# basic_micro.net
KiCad netlist of a schematic drawn in EAGLE
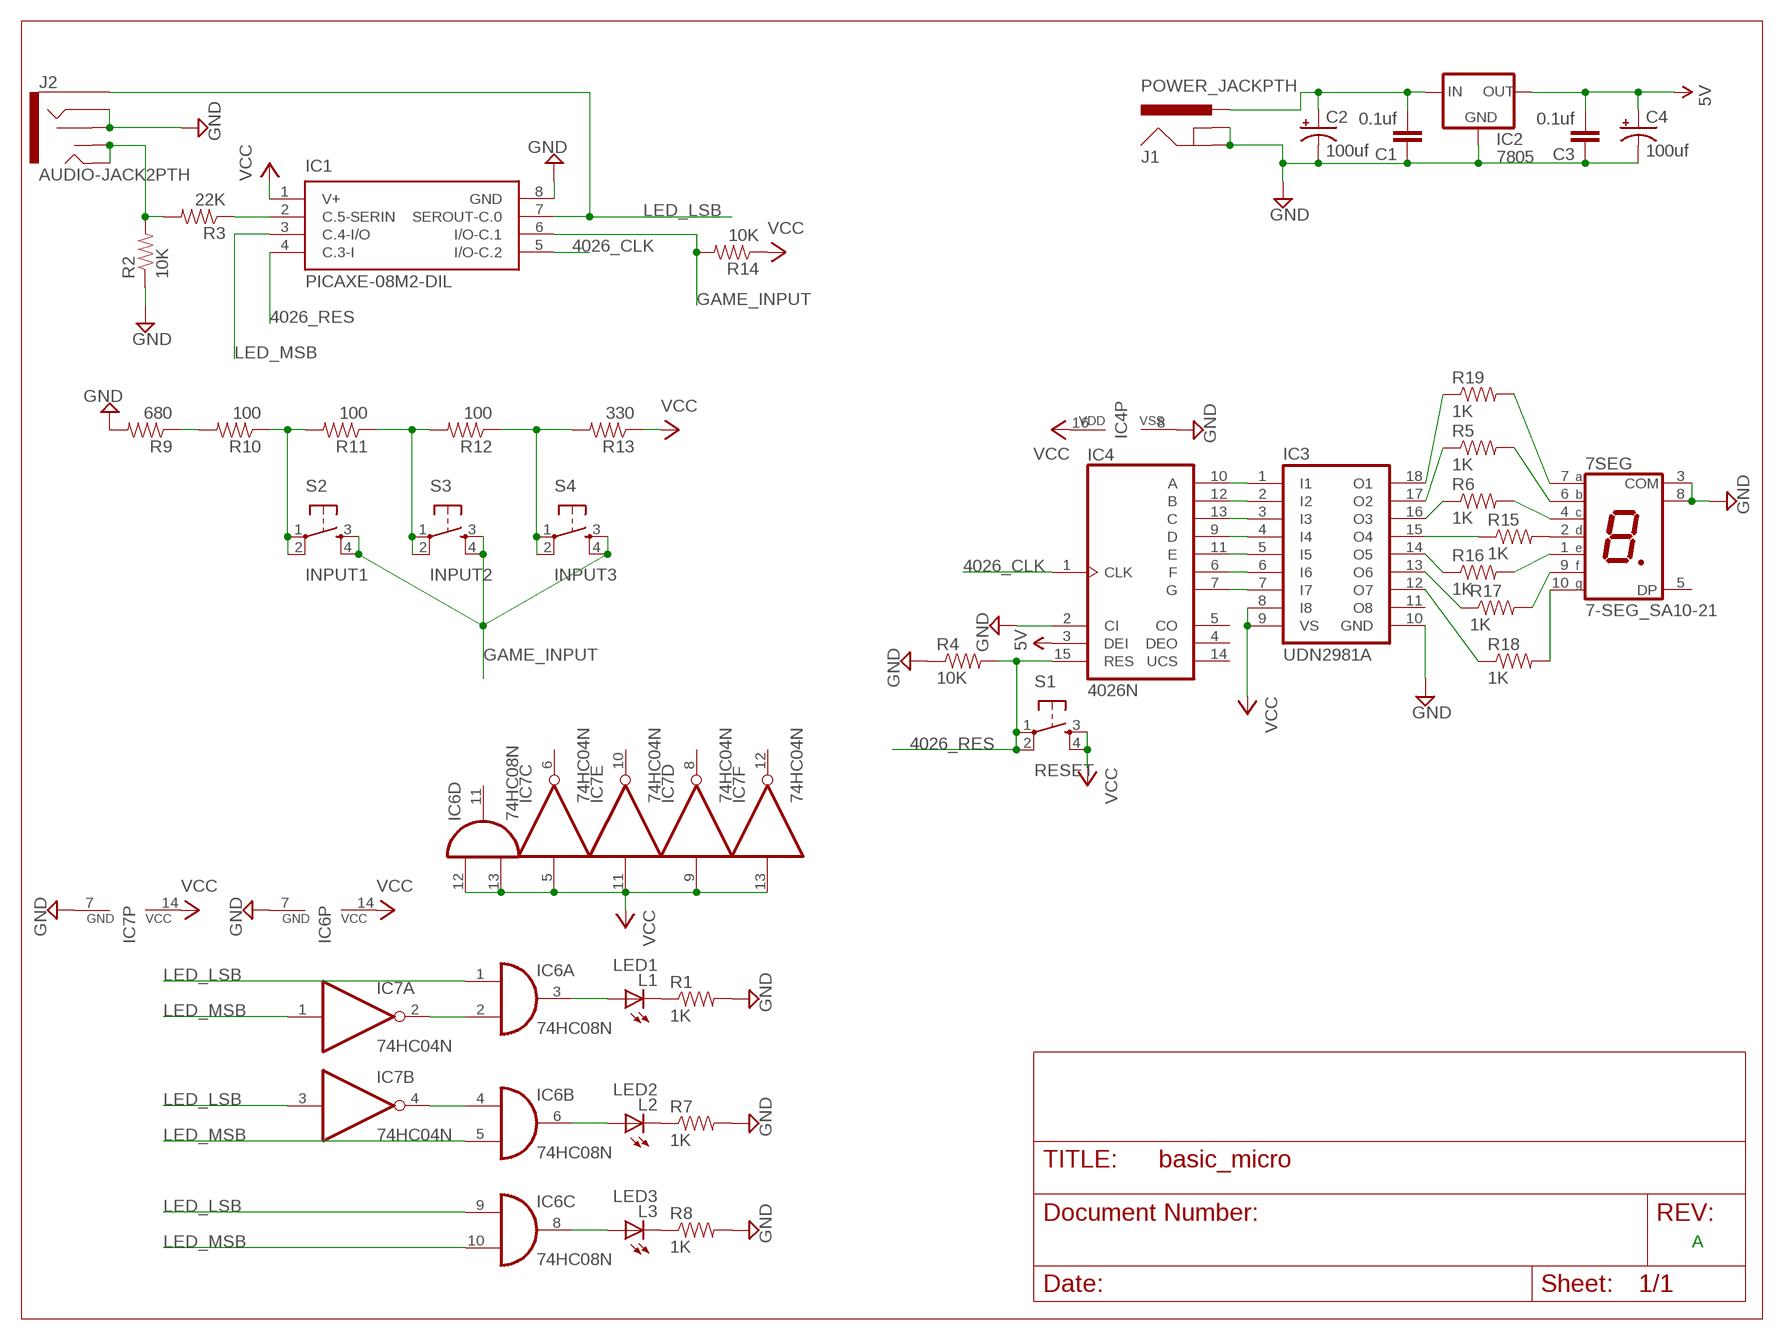
[diagram p0: schematic, sheet 1]

(export (version "E")
  (design (tool "Eeschema 10.0.6"))
  (components
    (comp (ref "7SEG")
      (value "7-SEG_SA10-21")
      (footprint "eagle-import:SA10-21")
      (libsource (lib "eagle-import") (part "7-SEG_SA10-21"))
    )
    (comp (ref "C1")
      (value "0.1uf")
      (footprint "eagle-import:C025-025X050")
      (libsource (lib "eagle-import") (part "C-EU025-025X050"))
    )
    (comp (ref "C2")
      (value "100uf")
      (footprint "eagle-import:ETR3")
      (libsource (lib "eagle-import") (part "CPOL-USETR3"))
    )
    (comp (ref "C3")
      (value "0.1uf")
      (footprint "eagle-import:C025-025X050")
      (libsource (lib "eagle-import") (part "C-EU025-025X050"))
    )
    (comp (ref "C4")
      (value "100uf")
      (footprint "eagle-import:ETR3")
      (libsource (lib "eagle-import") (part "CPOL-USETR3"))
    )
    (comp (ref "IC1")
      (value "PICAXE-08M2-DIL")
      (footprint "eagle-import:DIL8")
      (libsource (lib "eagle-import") (part "PICAXE-08M2-DIL"))
    )
    (comp (ref "IC2")
      (value "7805")
      (footprint "eagle-import:78XXL")
      (libsource (lib "eagle-import") (part "78XXL"))
    )
    (comp (ref "IC3")
      (value "UDN2981A")
      (footprint "eagle-import:DIL18")
      (libsource (lib "eagle-import") (part "UDN298A1"))
    )
    (comp (ref "IC4")
      (value "4026N")
      (footprint "eagle-import:DIL16")
      (libsource (lib "eagle-import") (part "4026N"))
    )
    (comp (ref "IC6")
      (value "74HC08N")
      (footprint "eagle-import:DIL14")
      (libsource (lib "eagle-import") (part "7408NHC"))
    )
    (comp (ref "IC7")
      (value "74HC04N")
      (footprint "eagle-import:DIL14")
      (libsource (lib "eagle-import") (part "7404NHC"))
    )
    (comp (ref "J1")
      (value "POWER_JACKPTH")
      (footprint "eagle-import:POWER_JACK_PTH")
      (libsource (lib "eagle-import") (part "POWER_JACKPTH"))
    )
    (comp (ref "J2")
      (value "AUDIO-JACK2PTH")
      (footprint "eagle-import:AUDIO-JACK")
      (libsource (lib "eagle-import") (part "AUDIO-JACK2PTH"))
    )
    (comp (ref "L1")
      (value "LED1")
      (footprint "eagle-import:LED3MM")
      (libsource (lib "eagle-import") (part "LED3MM"))
    )
    (comp (ref "L2")
      (value "LED2")
      (footprint "eagle-import:LED3MM")
      (libsource (lib "eagle-import") (part "LED3MM"))
    )
    (comp (ref "L3")
      (value "LED3")
      (footprint "eagle-import:LED3MM")
      (libsource (lib "eagle-import") (part "LED3MM"))
    )
    (comp (ref "R1")
      (value "1K")
      (footprint "eagle-import:AXIAL-0.4")
      (libsource (lib "eagle-import") (part "RESISTORPTH-1/4W"))
    )
    (comp (ref "R2")
      (value "10K")
      (footprint "eagle-import:AXIAL-0.4")
      (libsource (lib "eagle-import") (part "RESISTORPTH-1/4W"))
    )
    (comp (ref "R3")
      (value "22K")
      (footprint "eagle-import:AXIAL-0.4")
      (libsource (lib "eagle-import") (part "RESISTORPTH-1/4W"))
    )
    (comp (ref "R4")
      (value "10K")
      (footprint "eagle-import:AXIAL-0.4")
      (libsource (lib "eagle-import") (part "RESISTORPTH-1/4W"))
    )
    (comp (ref "R5")
      (value "1K")
      (footprint "eagle-import:AXIAL-0.4")
      (libsource (lib "eagle-import") (part "RESISTORPTH-1/4W"))
    )
    (comp (ref "R6")
      (value "1K")
      (footprint "eagle-import:AXIAL-0.4")
      (libsource (lib "eagle-import") (part "RESISTORPTH-1/4W"))
    )
    (comp (ref "R7")
      (value "1K")
      (footprint "eagle-import:AXIAL-0.4")
      (libsource (lib "eagle-import") (part "RESISTORPTH-1/4W"))
    )
    (comp (ref "R8")
      (value "1K")
      (footprint "eagle-import:AXIAL-0.4")
      (libsource (lib "eagle-import") (part "RESISTORPTH-1/4W"))
    )
    (comp (ref "R9")
      (value "680")
      (footprint "eagle-import:AXIAL-0.4")
      (libsource (lib "eagle-import") (part "RESISTORPTH-1/4W"))
    )
    (comp (ref "R10")
      (value "100")
      (footprint "eagle-import:AXIAL-0.4")
      (libsource (lib "eagle-import") (part "RESISTORPTH-1/4W"))
    )
    (comp (ref "R11")
      (value "100")
      (footprint "eagle-import:AXIAL-0.4")
      (libsource (lib "eagle-import") (part "RESISTORPTH-1/4W"))
    )
    (comp (ref "R12")
      (value "100")
      (footprint "eagle-import:AXIAL-0.4")
      (libsource (lib "eagle-import") (part "RESISTORPTH-1/4W"))
    )
    (comp (ref "R13")
      (value "330")
      (footprint "eagle-import:AXIAL-0.4")
      (libsource (lib "eagle-import") (part "RESISTORPTH-1/4W"))
    )
    (comp (ref "R14")
      (value "10K")
      (footprint "eagle-import:AXIAL-0.4")
      (libsource (lib "eagle-import") (part "RESISTORPTH-1/4W"))
    )
    (comp (ref "R15")
      (value "1K")
      (footprint "eagle-import:AXIAL-0.4")
      (libsource (lib "eagle-import") (part "RESISTORPTH-1/4W"))
    )
    (comp (ref "R16")
      (value "1K")
      (footprint "eagle-import:AXIAL-0.4")
      (libsource (lib "eagle-import") (part "RESISTORPTH-1/4W"))
    )
    (comp (ref "R17")
      (value "1K")
      (footprint "eagle-import:AXIAL-0.4")
      (libsource (lib "eagle-import") (part "RESISTORPTH-1/4W"))
    )
    (comp (ref "R18")
      (value "1K")
      (footprint "eagle-import:AXIAL-0.4")
      (libsource (lib "eagle-import") (part "RESISTORPTH-1/4W"))
    )
    (comp (ref "R19")
      (value "1K")
      (footprint "eagle-import:AXIAL-0.4")
      (libsource (lib "eagle-import") (part "RESISTORPTH-1/4W"))
    )
    (comp (ref "S1")
      (value "RESET")
      (footprint "eagle-import:TACTILE-PTH")
      (libsource (lib "eagle-import") (part "TAC_SWITCHPTH"))
    )
    (comp (ref "S2")
      (value "INPUT1")
      (footprint "eagle-import:TACTILE-PTH")
      (libsource (lib "eagle-import") (part "TAC_SWITCHPTH"))
    )
    (comp (ref "S3")
      (value "INPUT2")
      (footprint "eagle-import:TACTILE-PTH")
      (libsource (lib "eagle-import") (part "TAC_SWITCHPTH"))
    )
    (comp (ref "S4")
      (value "INPUT3")
      (footprint "eagle-import:TACTILE-PTH")
      (libsource (lib "eagle-import") (part "TAC_SWITCHPTH"))
    )
  )
  (nets
    (net (code "1") (name "/4026_CLK") (class "Default")
      (node (ref "IC1") (pin "5") (pinfunction "I/O-C.2_5") (pintype "bidirectional"))
      (node (ref "IC4") (pin "1") (pinfunction "CLK_1") (pintype "input"))
    )
    (net (code "2") (name "/4026_RES") (class "Default")
      (node (ref "IC1") (pin "4") (pinfunction "C.3-I_4") (pintype "input"))
      (node (ref "IC4") (pin "15") (pinfunction "RES_15") (pintype "input"))
      (node (ref "R4") (pin "P$2") (pinfunction "2_P$2") (pintype "passive"))
      (node (ref "S1") (pin "1") (pinfunction "1_1") (pintype "passive"))
      (node (ref "S1") (pin "2") (pinfunction "2_2") (pintype "passive"))
    )
    (net (code "3") (name "/GAME_INPUT") (class "Default")
      (node (ref "IC1") (pin "6") (pinfunction "I/O-C.1_6") (pintype "bidirectional"))
      (node (ref "R14") (pin "P$2") (pinfunction "2_P$2") (pintype "passive"))
      (node (ref "S2") (pin "3") (pinfunction "3_3") (pintype "passive"))
      (node (ref "S2") (pin "4") (pinfunction "4_4") (pintype "passive"))
      (node (ref "S3") (pin "3") (pinfunction "3_3") (pintype "passive"))
      (node (ref "S3") (pin "4") (pinfunction "4_4") (pintype "passive"))
      (node (ref "S4") (pin "3") (pinfunction "3_3") (pintype "passive"))
      (node (ref "S4") (pin "4") (pinfunction "4_4") (pintype "passive"))
    )
    (net (code "4") (name "/LED_LSB") (class "Default")
      (node (ref "IC1") (pin "7") (pinfunction "SEROUT-C.0_7") (pintype "output"))
      (node (ref "IC6") (pin "1") (pinfunction "I0_1") (pintype "input"))
      (node (ref "IC6") (pin "9") (pinfunction "I0_9") (pintype "input"))
      (node (ref "IC7") (pin "3") (pinfunction "I_3") (pintype "input"))
      (node (ref "J2") (pin "SLEEVE") (pinfunction "SLEEVE_SLEEVE") (pintype "bidirectional"))
    )
    (net (code "5") (name "/LED_MSB") (class "Default")
      (node (ref "IC1") (pin "3") (pinfunction "C.4-I/O_3") (pintype "bidirectional"))
      (node (ref "IC6") (pin "10") (pinfunction "I1_10") (pintype "input"))
      (node (ref "IC6") (pin "5") (pinfunction "I1_5") (pintype "input"))
      (node (ref "IC7") (pin "1") (pinfunction "I_1") (pintype "input"))
    )
    (net (code "6") (name "5V") (class "Default")
      (node (ref "C3") (pin "2") (pinfunction "2_2") (pintype "passive"))
      (node (ref "C4") (pin "+") (pinfunction "+_+") (pintype "passive"))
      (node (ref "IC2") (pin "OUT") (pinfunction "OUT_OUT") (pintype "passive"))
      (node (ref "IC4") (pin "3") (pinfunction "DEI_3") (pintype "input"))
    )
    (net (code "7") (name "GND") (class "Default")
      (node (ref "7SEG") (pin "3") (pinfunction "COM_3") (pintype "passive"))
      (node (ref "7SEG") (pin "8") (pinfunction "COM_8") (pintype "passive"))
      (node (ref "C1") (pin "1") (pinfunction "1_1") (pintype "passive"))
      (node (ref "C2") (pin "-") (pinfunction "-_-") (pintype "passive"))
      (node (ref "C3") (pin "1") (pinfunction "1_1") (pintype "passive"))
      (node (ref "C4") (pin "-") (pinfunction "-_-") (pintype "passive"))
      (node (ref "IC1") (pin "8") (pinfunction "GND_8") (pintype "power_in"))
      (node (ref "IC2") (pin "GND") (pinfunction "GND_GND") (pintype "input"))
      (node (ref "IC3") (pin "10") (pinfunction "GND_10") (pintype "power_in"))
      (node (ref "IC4") (pin "2") (pinfunction "CI_2") (pintype "input"))
      (node (ref "IC4") (pin "8") (pinfunction "VSS_8") (pintype "power_in"))
      (node (ref "IC6") (pin "7") (pinfunction "GND_7") (pintype "power_in"))
      (node (ref "IC7") (pin "7") (pinfunction "GND_7") (pintype "power_in"))
      (node (ref "J1") (pin "GND") (pinfunction "GND_GND") (pintype "bidirectional"))
      (node (ref "J1") (pin "GNDBREAK") (pinfunction "GNDBREAK_GNDBREAK") (pintype "bidirectional"))
      (node (ref "J2") (pin "RING") (pinfunction "RING_RING") (pintype "bidirectional"))
      (node (ref "J2") (pin "RSH") (pinfunction "RSH_RSH") (pintype "bidirectional"))
      (node (ref "R1") (pin "P$2") (pinfunction "2_P$2") (pintype "passive"))
      (node (ref "R2") (pin "P$1") (pinfunction "1_P$1") (pintype "passive"))
      (node (ref "R4") (pin "P$1") (pinfunction "1_P$1") (pintype "passive"))
      (node (ref "R7") (pin "P$2") (pinfunction "2_P$2") (pintype "passive"))
      (node (ref "R8") (pin "P$2") (pinfunction "2_P$2") (pintype "passive"))
      (node (ref "R9") (pin "P$2") (pinfunction "2_P$2") (pintype "passive"))
    )
    (net (code "8") (name "Net-(7SEG-A)") (class "Default")
      (node (ref "7SEG") (pin "7") (pinfunction "A_7") (pintype "passive"))
      (node (ref "R19") (pin "P$2") (pinfunction "2_P$2") (pintype "passive"))
    )
    (net (code "9") (name "Net-(7SEG-B)") (class "Default")
      (node (ref "7SEG") (pin "6") (pinfunction "B_6") (pintype "passive"))
      (node (ref "R5") (pin "P$2") (pinfunction "2_P$2") (pintype "passive"))
    )
    (net (code "10") (name "Net-(7SEG-C)") (class "Default")
      (node (ref "7SEG") (pin "4") (pinfunction "C_4") (pintype "passive"))
      (node (ref "R6") (pin "P$2") (pinfunction "2_P$2") (pintype "passive"))
    )
    (net (code "11") (name "Net-(7SEG-D)") (class "Default")
      (node (ref "7SEG") (pin "2") (pinfunction "D_2") (pintype "passive"))
      (node (ref "R15") (pin "P$2") (pinfunction "2_P$2") (pintype "passive"))
    )
    (net (code "12") (name "Net-(7SEG-E)") (class "Default")
      (node (ref "7SEG") (pin "1") (pinfunction "E_1") (pintype "passive"))
      (node (ref "R16") (pin "P$2") (pinfunction "2_P$2") (pintype "passive"))
    )
    (net (code "13") (name "Net-(7SEG-F)") (class "Default")
      (node (ref "7SEG") (pin "9") (pinfunction "F_9") (pintype "passive"))
      (node (ref "R17") (pin "P$2") (pinfunction "2_P$2") (pintype "passive"))
    )
    (net (code "14") (name "Net-(7SEG-G)") (class "Default")
      (node (ref "7SEG") (pin "10") (pinfunction "G_10") (pintype "passive"))
      (node (ref "R18") (pin "P$2") (pinfunction "2_P$2") (pintype "passive"))
    )
    (net (code "15") (name "Net-(C1-Pad2)") (class "Default")
      (node (ref "C1") (pin "2") (pinfunction "2_2") (pintype "passive"))
      (node (ref "C2") (pin "+") (pinfunction "+_+") (pintype "passive"))
      (node (ref "IC2") (pin "IN") (pinfunction "IN_IN") (pintype "input"))
      (node (ref "J1") (pin "PWR") (pinfunction "PWR_PWR") (pintype "bidirectional"))
    )
    (net (code "16") (name "Net-(IC1-C.5-SERIN)") (class "Default")
      (node (ref "IC1") (pin "2") (pinfunction "C.5-SERIN_2") (pintype "input"))
      (node (ref "R3") (pin "P$1") (pinfunction "1_P$1") (pintype "passive"))
    )
    (net (code "17") (name "Net-(IC3-I1)") (class "Default")
      (node (ref "IC3") (pin "1") (pinfunction "I1_1") (pintype "input"))
      (node (ref "IC4") (pin "10") (pinfunction "A_10") (pintype "output"))
    )
    (net (code "18") (name "Net-(IC3-I2)") (class "Default")
      (node (ref "IC3") (pin "2") (pinfunction "I2_2") (pintype "input"))
      (node (ref "IC4") (pin "12") (pinfunction "B_12") (pintype "output"))
    )
    (net (code "19") (name "Net-(IC3-I3)") (class "Default")
      (node (ref "IC3") (pin "3") (pinfunction "I3_3") (pintype "input"))
      (node (ref "IC4") (pin "13") (pinfunction "C_13") (pintype "output"))
    )
    (net (code "20") (name "Net-(IC3-I4)") (class "Default")
      (node (ref "IC3") (pin "4") (pinfunction "I4_4") (pintype "input"))
      (node (ref "IC4") (pin "9") (pinfunction "D_9") (pintype "output"))
    )
    (net (code "21") (name "Net-(IC3-I5)") (class "Default")
      (node (ref "IC3") (pin "5") (pinfunction "I5_5") (pintype "input"))
      (node (ref "IC4") (pin "11") (pinfunction "E_11") (pintype "output"))
    )
    (net (code "22") (name "Net-(IC3-I6)") (class "Default")
      (node (ref "IC3") (pin "6") (pinfunction "I6_6") (pintype "input"))
      (node (ref "IC4") (pin "6") (pinfunction "F_6") (pintype "output"))
    )
    (net (code "23") (name "Net-(IC3-I7)") (class "Default")
      (node (ref "IC3") (pin "7") (pinfunction "I7_7") (pintype "input"))
      (node (ref "IC4") (pin "7") (pinfunction "G_7") (pintype "output"))
    )
    (net (code "24") (name "Net-(IC3-O1)") (class "Default")
      (node (ref "IC3") (pin "18") (pinfunction "O1_18") (pintype "open_collector"))
      (node (ref "R19") (pin "P$1") (pinfunction "1_P$1") (pintype "passive"))
    )
    (net (code "25") (name "Net-(IC3-O2)") (class "Default")
      (node (ref "IC3") (pin "17") (pinfunction "O2_17") (pintype "open_collector"))
      (node (ref "R5") (pin "P$1") (pinfunction "1_P$1") (pintype "passive"))
    )
    (net (code "26") (name "Net-(IC3-O3)") (class "Default")
      (node (ref "IC3") (pin "16") (pinfunction "O3_16") (pintype "open_collector"))
      (node (ref "R6") (pin "P$1") (pinfunction "1_P$1") (pintype "passive"))
    )
    (net (code "27") (name "Net-(IC3-O4)") (class "Default")
      (node (ref "IC3") (pin "15") (pinfunction "O4_15") (pintype "open_collector"))
      (node (ref "R15") (pin "P$1") (pinfunction "1_P$1") (pintype "passive"))
    )
    (net (code "28") (name "Net-(IC3-O5)") (class "Default")
      (node (ref "IC3") (pin "14") (pinfunction "O5_14") (pintype "open_collector"))
      (node (ref "R16") (pin "P$1") (pinfunction "1_P$1") (pintype "passive"))
    )
    (net (code "29") (name "Net-(IC3-O6)") (class "Default")
      (node (ref "IC3") (pin "13") (pinfunction "O6_13") (pintype "open_collector"))
      (node (ref "R17") (pin "P$1") (pinfunction "1_P$1") (pintype "passive"))
    )
    (net (code "30") (name "Net-(IC3-O7)") (class "Default")
      (node (ref "IC3") (pin "12") (pinfunction "O7_12") (pintype "open_collector"))
      (node (ref "R18") (pin "P$1") (pinfunction "1_P$1") (pintype "passive"))
    )
    (net (code "31") (name "Net-(IC6A-I1)") (class "Default")
      (node (ref "IC6") (pin "2") (pinfunction "I1_2") (pintype "input"))
      (node (ref "IC7") (pin "2") (pinfunction "O_2") (pintype "output"))
    )
    (net (code "32") (name "Net-(IC6A-O)") (class "Default")
      (node (ref "IC6") (pin "3") (pinfunction "O_3") (pintype "output"))
      (node (ref "L1") (pin "A") (pinfunction "A_A") (pintype "passive"))
    )
    (net (code "33") (name "Net-(IC6B-I0)") (class "Default")
      (node (ref "IC6") (pin "4") (pinfunction "I0_4") (pintype "input"))
      (node (ref "IC7") (pin "4") (pinfunction "O_4") (pintype "output"))
    )
    (net (code "34") (name "Net-(IC6B-O)") (class "Default")
      (node (ref "IC6") (pin "6") (pinfunction "O_6") (pintype "output"))
      (node (ref "L2") (pin "A") (pinfunction "A_A") (pintype "passive"))
    )
    (net (code "35") (name "Net-(IC6C-O)") (class "Default")
      (node (ref "IC6") (pin "8") (pinfunction "O_8") (pintype "output"))
      (node (ref "L3") (pin "A") (pinfunction "A_A") (pintype "passive"))
    )
    (net (code "36") (name "Net-(L1-C)") (class "Default")
      (node (ref "L1") (pin "K") (pinfunction "C_K") (pintype "passive"))
      (node (ref "R1") (pin "P$1") (pinfunction "1_P$1") (pintype "passive"))
    )
    (net (code "37") (name "Net-(L2-C)") (class "Default")
      (node (ref "L2") (pin "K") (pinfunction "C_K") (pintype "passive"))
      (node (ref "R7") (pin "P$1") (pinfunction "1_P$1") (pintype "passive"))
    )
    (net (code "38") (name "Net-(L3-C)") (class "Default")
      (node (ref "L3") (pin "K") (pinfunction "C_K") (pintype "passive"))
      (node (ref "R8") (pin "P$1") (pinfunction "1_P$1") (pintype "passive"))
    )
    (net (code "39") (name "Net-(R2-2)") (class "Default")
      (node (ref "J2") (pin "TIP") (pinfunction "TIP_TIP") (pintype "bidirectional"))
      (node (ref "J2") (pin "TSH") (pinfunction "TSH_TSH") (pintype "bidirectional"))
      (node (ref "R2") (pin "P$2") (pinfunction "2_P$2") (pintype "passive"))
      (node (ref "R3") (pin "P$2") (pinfunction "2_P$2") (pintype "passive"))
    )
    (net (code "40") (name "Net-(R10-1)") (class "Default")
      (node (ref "R10") (pin "P$1") (pinfunction "1_P$1") (pintype "passive"))
      (node (ref "R11") (pin "P$2") (pinfunction "2_P$2") (pintype "passive"))
      (node (ref "S2") (pin "1") (pinfunction "1_1") (pintype "passive"))
      (node (ref "S2") (pin "2") (pinfunction "2_2") (pintype "passive"))
    )
    (net (code "41") (name "Net-(R10-2)") (class "Default")
      (node (ref "R10") (pin "P$2") (pinfunction "2_P$2") (pintype "passive"))
      (node (ref "R9") (pin "P$1") (pinfunction "1_P$1") (pintype "passive"))
    )
    (net (code "42") (name "Net-(R11-1)") (class "Default")
      (node (ref "R11") (pin "P$1") (pinfunction "1_P$1") (pintype "passive"))
      (node (ref "R12") (pin "P$2") (pinfunction "2_P$2") (pintype "passive"))
      (node (ref "S3") (pin "1") (pinfunction "1_1") (pintype "passive"))
      (node (ref "S3") (pin "2") (pinfunction "2_2") (pintype "passive"))
    )
    (net (code "43") (name "Net-(R12-1)") (class "Default")
      (node (ref "R12") (pin "P$1") (pinfunction "1_P$1") (pintype "passive"))
      (node (ref "R13") (pin "P$2") (pinfunction "2_P$2") (pintype "passive"))
      (node (ref "S4") (pin "1") (pinfunction "1_1") (pintype "passive"))
      (node (ref "S4") (pin "2") (pinfunction "2_2") (pintype "passive"))
    )
    (net (code "44") (name "VCC") (class "Default")
      (node (ref "IC1") (pin "1") (pinfunction "V+_1") (pintype "power_in"))
      (node (ref "IC3") (pin "8") (pinfunction "I8_8") (pintype "input"))
      (node (ref "IC3") (pin "9") (pinfunction "VS_9") (pintype "passive"))
      (node (ref "IC4") (pin "16") (pinfunction "VDD_16") (pintype "power_in"))
      (node (ref "IC6") (pin "12") (pinfunction "I0_12") (pintype "input"))
      (node (ref "IC6") (pin "13") (pinfunction "I1_13") (pintype "input"))
      (node (ref "IC6") (pin "14") (pinfunction "VCC_14") (pintype "power_in"))
      (node (ref "IC7") (pin "11") (pinfunction "I_11") (pintype "input"))
      (node (ref "IC7") (pin "13") (pinfunction "I_13") (pintype "input"))
      (node (ref "IC7") (pin "14") (pinfunction "VCC_14") (pintype "power_in"))
      (node (ref "IC7") (pin "5") (pinfunction "I_5") (pintype "input"))
      (node (ref "IC7") (pin "9") (pinfunction "I_9") (pintype "input"))
      (node (ref "R13") (pin "P$1") (pinfunction "1_P$1") (pintype "passive"))
      (node (ref "R14") (pin "P$1") (pinfunction "1_P$1") (pintype "passive"))
      (node (ref "S1") (pin "3") (pinfunction "3_3") (pintype "passive"))
      (node (ref "S1") (pin "4") (pinfunction "4_4") (pintype "passive"))
    )
    (net (code "45") (name "unconnected-(7SEG-DP-Pad5)") (class "Default")
      (node (ref "7SEG") (pin "5") (pinfunction "DP_5") (pintype "passive"))
    )
    (net (code "46") (name "unconnected-(IC3-O8-Pad11)") (class "Default")
      (node (ref "IC3") (pin "11") (pinfunction "O8_11") (pintype "open_collector"))
    )
    (net (code "47") (name "unconnected-(IC4A-CO-Pad5)") (class "Default")
      (node (ref "IC4") (pin "5") (pinfunction "CO_5") (pintype "output"))
    )
    (net (code "48") (name "unconnected-(IC4A-DEO-Pad4)") (class "Default")
      (node (ref "IC4") (pin "4") (pinfunction "DEO_4") (pintype "output"))
    )
    (net (code "49") (name "unconnected-(IC4A-UCS-Pad14)") (class "Default")
      (node (ref "IC4") (pin "14") (pinfunction "UCS_14") (pintype "output"))
    )
    (net (code "50") (name "unconnected-(IC6D-O-Pad11)") (class "Default")
      (node (ref "IC6") (pin "11") (pinfunction "O_11") (pintype "output"))
    )
    (net (code "51") (name "unconnected-(IC7C-O-Pad6)") (class "Default")
      (node (ref "IC7") (pin "6") (pinfunction "O_6") (pintype "output"))
    )
    (net (code "52") (name "unconnected-(IC7D-O-Pad8)") (class "Default")
      (node (ref "IC7") (pin "8") (pinfunction "O_8") (pintype "output"))
    )
    (net (code "53") (name "unconnected-(IC7E-O-Pad10)") (class "Default")
      (node (ref "IC7") (pin "10") (pinfunction "O_10") (pintype "output"))
    )
    (net (code "54") (name "unconnected-(IC7F-O-Pad12)") (class "Default")
      (node (ref "IC7") (pin "12") (pinfunction "O_12") (pintype "output"))
    )
  )
)
